# Top_rev1.net
KiCad netlist of a schematic drawn in EAGLE
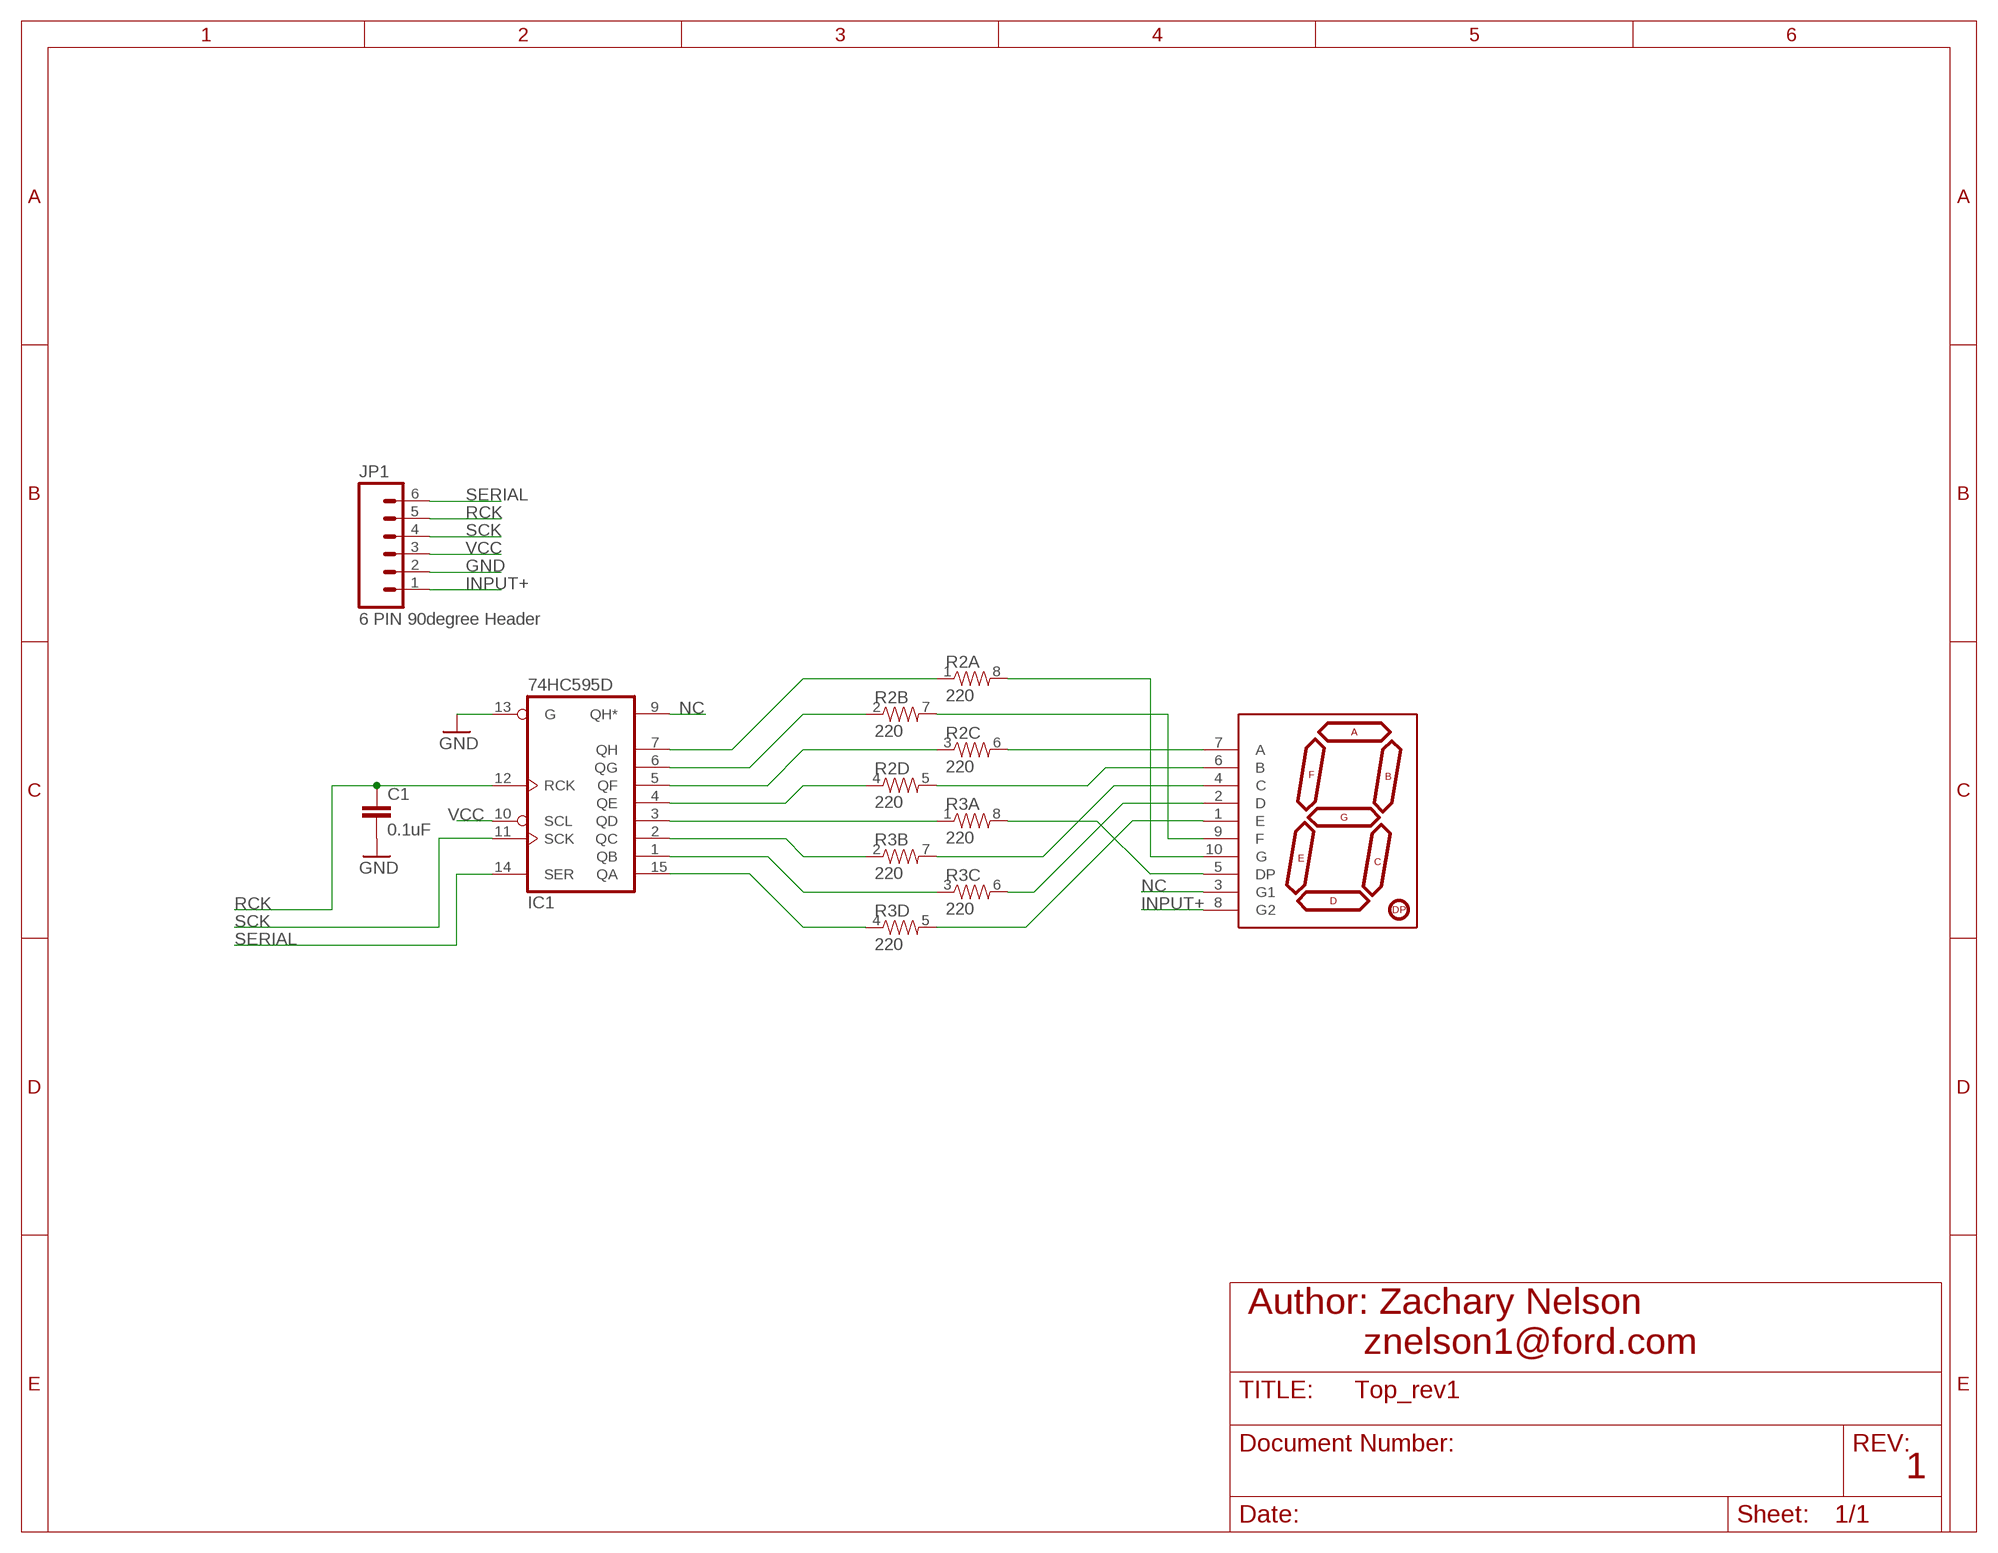
[diagram p0: schematic, sheet 1]

(export (version "E")
  (design (tool "Eeschema 10.0.6"))
  (components
    (comp (ref "C1")
      (value "0.1uF")
      (footprint "eagle-import:0402-CAP")
      (libsource (lib "eagle-import") (part "CAP0402-CAP"))
    )
    (comp (ref "IC1")
      (value "74HC595D")
      (footprint "eagle-import:SO16")
      (libsource (lib "eagle-import") (part "74595DHC"))
    )
    (comp (ref "JP1")
      (value "6 PIN 90degree Header")
      (footprint "eagle-import:1X06_HOLES_ONLY")
      (libsource (lib "eagle-import") (part "M06POGOPIN_HOLES_ONLY"))
    )
    (comp (ref "R2")
      (value "220")
      (footprint "eagle-import:0603-ARV")
      (libsource (lib "eagle-import") (part "RESISTOR-ARRAY0603-ARV"))
    )
    (comp (ref "R3")
      (value "220")
      (footprint "eagle-import:0603-ARV")
      (libsource (lib "eagle-import") (part "RESISTOR-ARRAY0603-ARV"))
    )
    (comp (ref "U$1")
      (value "7-SEGMENT-DISPLAY-1\"-RED")
      (footprint "eagle-import:7-SEGMENT-1_PTH")
      (libsource (lib "eagle-import") (part "7-SEGMENT-DISPLAY-1{dblquote}-RED"))
    )
  )
  (nets
    (net (code "1") (name "/INPUT+") (class "Default")
      (node (ref "JP1") (pin "1") (pinfunction "1_1") (pintype "passive"))
      (node (ref "U$1") (pin "8") (pinfunction "G2_8") (pintype "bidirectional"))
    )
    (net (code "2") (name "/NC") (class "Default")
      (node (ref "IC1") (pin "9") (pinfunction "QH*_9") (pintype "tri_state"))
      (node (ref "U$1") (pin "3") (pinfunction "G1_3") (pintype "bidirectional"))
    )
    (net (code "3") (name "/RCK") (class "Default")
      (node (ref "C1") (pin "1") (pinfunction "1_1") (pintype "passive"))
      (node (ref "IC1") (pin "12") (pinfunction "RCK_12") (pintype "input"))
      (node (ref "JP1") (pin "5") (pinfunction "5_5") (pintype "passive"))
    )
    (net (code "4") (name "/SCK") (class "Default")
      (node (ref "IC1") (pin "11") (pinfunction "SCK_11") (pintype "input"))
      (node (ref "JP1") (pin "4") (pinfunction "4_4") (pintype "passive"))
    )
    (net (code "5") (name "/SERIAL") (class "Default")
      (node (ref "IC1") (pin "14") (pinfunction "SER_14") (pintype "input"))
      (node (ref "JP1") (pin "6") (pinfunction "6_6") (pintype "passive"))
    )
    (net (code "6") (name "/VCC") (class "Default")
      (node (ref "IC1") (pin "10") (pinfunction "SCL_10") (pintype "input"))
      (node (ref "JP1") (pin "3") (pinfunction "3_3") (pintype "passive"))
    )
    (net (code "7") (name "GND") (class "Default")
      (node (ref "C1") (pin "2") (pinfunction "2_2") (pintype "passive"))
      (node (ref "IC1") (pin "13") (pinfunction "G_13") (pintype "input"))
      (node (ref "JP1") (pin "2") (pinfunction "2_2") (pintype "passive"))
    )
    (net (code "8") (name "Net-(IC1A-QA)") (class "Default")
      (node (ref "IC1") (pin "15") (pinfunction "QA_15") (pintype "tri_state"))
      (node (ref "R3") (pin "4") (pinfunction "1_4") (pintype "passive"))
    )
    (net (code "9") (name "Net-(IC1A-QB)") (class "Default")
      (node (ref "IC1") (pin "1") (pinfunction "QB_1") (pintype "tri_state"))
      (node (ref "R3") (pin "3") (pinfunction "1_3") (pintype "passive"))
    )
    (net (code "10") (name "Net-(IC1A-QC)") (class "Default")
      (node (ref "IC1") (pin "2") (pinfunction "QC_2") (pintype "tri_state"))
      (node (ref "R3") (pin "2") (pinfunction "1_2") (pintype "passive"))
    )
    (net (code "11") (name "Net-(IC1A-QD)") (class "Default")
      (node (ref "IC1") (pin "3") (pinfunction "QD_3") (pintype "tri_state"))
      (node (ref "R3") (pin "1") (pinfunction "1_1") (pintype "passive"))
    )
    (net (code "12") (name "Net-(IC1A-QE)") (class "Default")
      (node (ref "IC1") (pin "4") (pinfunction "QE_4") (pintype "tri_state"))
      (node (ref "R2") (pin "4") (pinfunction "1_4") (pintype "passive"))
    )
    (net (code "13") (name "Net-(IC1A-QF)") (class "Default")
      (node (ref "IC1") (pin "5") (pinfunction "QF_5") (pintype "tri_state"))
      (node (ref "R2") (pin "3") (pinfunction "1_3") (pintype "passive"))
    )
    (net (code "14") (name "Net-(IC1A-QG)") (class "Default")
      (node (ref "IC1") (pin "6") (pinfunction "QG_6") (pintype "tri_state"))
      (node (ref "R2") (pin "2") (pinfunction "1_2") (pintype "passive"))
    )
    (net (code "15") (name "Net-(IC1A-QH)") (class "Default")
      (node (ref "IC1") (pin "7") (pinfunction "QH_7") (pintype "tri_state"))
      (node (ref "R2") (pin "1") (pinfunction "1_1") (pintype "passive"))
    )
    (net (code "16") (name "Net-(R2A-2)") (class "Default")
      (node (ref "R2") (pin "8") (pinfunction "2_8") (pintype "passive"))
      (node (ref "U$1") (pin "10") (pinfunction "G_10") (pintype "bidirectional"))
    )
    (net (code "17") (name "Net-(R2B-2)") (class "Default")
      (node (ref "R2") (pin "7") (pinfunction "2_7") (pintype "passive"))
      (node (ref "U$1") (pin "9") (pinfunction "F_9") (pintype "bidirectional"))
    )
    (net (code "18") (name "Net-(R2C-2)") (class "Default")
      (node (ref "R2") (pin "6") (pinfunction "2_6") (pintype "passive"))
      (node (ref "U$1") (pin "7") (pinfunction "A_7") (pintype "bidirectional"))
    )
    (net (code "19") (name "Net-(R2D-2)") (class "Default")
      (node (ref "R2") (pin "5") (pinfunction "2_5") (pintype "passive"))
      (node (ref "U$1") (pin "6") (pinfunction "B_6") (pintype "bidirectional"))
    )
    (net (code "20") (name "Net-(R3A-2)") (class "Default")
      (node (ref "R3") (pin "8") (pinfunction "2_8") (pintype "passive"))
      (node (ref "U$1") (pin "5") (pinfunction "DP_5") (pintype "bidirectional"))
    )
    (net (code "21") (name "Net-(R3B-2)") (class "Default")
      (node (ref "R3") (pin "7") (pinfunction "2_7") (pintype "passive"))
      (node (ref "U$1") (pin "4") (pinfunction "C_4") (pintype "bidirectional"))
    )
    (net (code "22") (name "Net-(R3C-2)") (class "Default")
      (node (ref "R3") (pin "6") (pinfunction "2_6") (pintype "passive"))
      (node (ref "U$1") (pin "2") (pinfunction "D_2") (pintype "bidirectional"))
    )
    (net (code "23") (name "Net-(R3D-2)") (class "Default")
      (node (ref "R3") (pin "5") (pinfunction "2_5") (pintype "passive"))
      (node (ref "U$1") (pin "1") (pinfunction "E_1") (pintype "bidirectional"))
    )
  )
)
